# PSU5V-400mA.net
KiCad netlist of a schematic drawn in Altium Designer
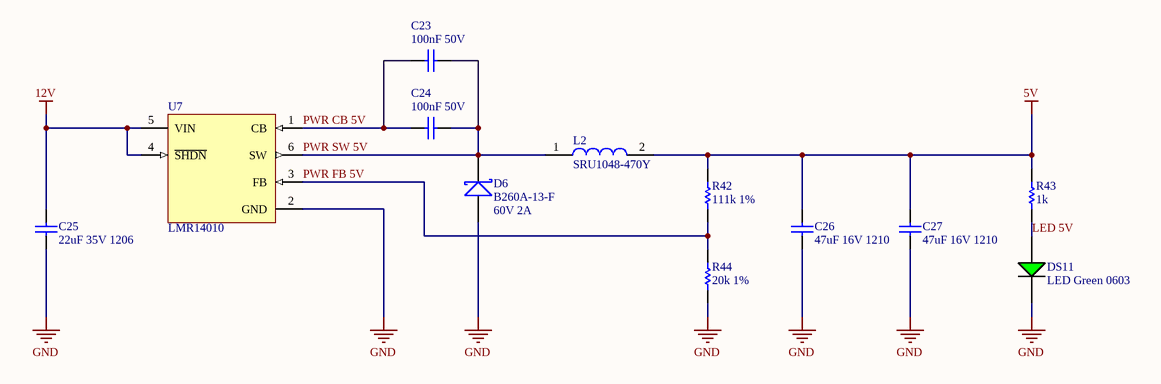
[diagram p0: PSU5V-400mA.SchDoc]

(export (version "E")
  (design (tool "Eeschema 10.0.6"))
  (components
    (comp (ref "C23")
      (value "100nF 50V")
      (footprint "Cap_Ceramic_0603")
      (description "Capacitor, Ceramic, SMD, 100nF, 50V, 5%, X7R, 0603")
      (libsource (lib "StandardCapacitors") (part "100nF 50V 5% X7R 0603"))
    )
    (comp (ref "C24")
      (value "100nF 50V")
      (footprint "Cap_Ceramic_0603")
      (description "Capacitor, Ceramic, SMD, 100nF, 50V, 5%, X7R, 0603")
      (libsource (lib "StandardCapacitors") (part "100nF 50V 5% X7R 0603"))
    )
    (comp (ref "C25")
      (value "22uF 35V 1206")
      (footprint "Cap_Ceramic_1206")
      (description "Capacitor, Ceramic, SMD, 22uF, 35V, 10%, X7R, 1206")
      (libsource (lib "StandardCapacitors") (part "22uF 35V 10% X7R 1206"))
    )
    (comp (ref "C26")
      (value "47uF 16V 1210")
      (footprint "Cap_Ceramic_1210")
      (description "Capacitor, Ceramic, SMD, 47uF, 16V, 5%, X7R, 1210")
      (libsource (lib "StandardCapacitors") (part "47uF 16V 10% X7R 1210"))
    )
    (comp (ref "C27")
      (value "47uF 16V 1210")
      (footprint "Cap_Ceramic_1210")
      (description "Capacitor, Ceramic, SMD, 47uF, 16V, 5%, X7R, 1210")
      (libsource (lib "StandardCapacitors") (part "47uF 16V 10% X7R 1210"))
    )
    (comp (ref "D6")
      (value "B260A-13-F")
      (footprint "SMA")
      (description "Diode, Schottky Barrier Rectifier, 60 V, 2 A, B260A-13-F")
      (libsource (lib "QUTMS_DiodeLibrary") (part "B260A-13-F"))
    )
    (comp (ref "DS11")
      (value "LED Green 0603")
      (footprint "LED GREEN 0603")
      (libsource (lib "QUTMS_LEDLibrary") (part "LED Green 0603"))
    )
    (comp (ref "L2")
      (value "SRU1048-470Y")
      (footprint "SRU1048")
      (description "Fixed Inductors 47uH 30% SMD 1048")
      (libsource (lib "QUTMS_InductorLibrary") (part "SRU1048-470Y"))
    )
    (comp (ref "R42")
      (value "111k 1%")
      (footprint "Res_ThinFilm_0603")
      (description "Resistor, SMD, 111k, 0.1W, 5%, 0603")
      (libsource (lib "StandardResistors") (part "111k 1% 0603"))
    )
    (comp (ref "R43")
      (value "1k")
      (footprint "Res_ThinFilm_0603")
      (description "Resistor, SMD, 1k, 0.1W, 5%, 0603")
      (libsource (lib "StandardResistors") (part "1k 5% 0603"))
    )
    (comp (ref "R44")
      (value "20k 1%")
      (footprint "Res_ThinFilm_0603")
      (description "Resistor, SMD, 20k, 0.1W, 1%, 0603")
      (libsource (lib "StandardResistors") (part "20k 1% 0603"))
    )
    (comp (ref "U7")
      (value "LMR14010")
      (footprint "LMR14010")
      (libsource (lib "QUTMS_PowerSupplyLibrary") (part "LMR14010"))
    )
  )
  (nets
    (net (code "1") (name "/LED 5V") (class "Default")
      (node (ref "DS11") (pin "1") (pinfunction "A_1") (pintype "passive"))
      (node (ref "R43") (pin "1") (pinfunction "1_1") (pintype "passive"))
    )
    (net (code "2") (name "/PWR CB 5V") (class "Default")
      (node (ref "C23") (pin "1") (pinfunction "1_1") (pintype "passive"))
      (node (ref "C24") (pin "1") (pinfunction "1_1") (pintype "passive"))
      (node (ref "U7") (pin "1") (pinfunction "CB_1") (pintype "input"))
    )
    (net (code "3") (name "/PWR FB 5V") (class "Default")
      (node (ref "R42") (pin "1") (pinfunction "1_1") (pintype "passive"))
      (node (ref "R44") (pin "2") (pinfunction "2_2") (pintype "passive"))
      (node (ref "U7") (pin "3") (pinfunction "FB_3") (pintype "input"))
    )
    (net (code "4") (name "/PWR SW 5V") (class "Default")
      (node (ref "C23") (pin "2") (pinfunction "2_2") (pintype "passive"))
      (node (ref "C24") (pin "2") (pinfunction "2_2") (pintype "passive"))
      (node (ref "D6") (pin "K") (pinfunction "K_K") (pintype "passive"))
      (node (ref "L2") (pin "1") (pinfunction "1_1") (pintype "passive"))
      (node (ref "U7") (pin "6") (pinfunction "SW_6") (pintype "output"))
    )
    (net (code "5") (name "5V") (class "Default")
      (node (ref "C26") (pin "2") (pinfunction "2_2") (pintype "passive"))
      (node (ref "C27") (pin "2") (pinfunction "2_2") (pintype "passive"))
      (node (ref "L2") (pin "2") (pinfunction "2_2") (pintype "passive"))
      (node (ref "R42") (pin "2") (pinfunction "2_2") (pintype "passive"))
      (node (ref "R43") (pin "2") (pinfunction "2_2") (pintype "passive"))
    )
    (net (code "6") (name "12V") (class "Default")
      (node (ref "C25") (pin "2") (pinfunction "2_2") (pintype "passive"))
      (node (ref "U7") (pin "4") (pinfunction "~{SHDN}_4") (pintype "input"))
      (node (ref "U7") (pin "5") (pinfunction "VIN_5") (pintype "power_in"))
    )
    (net (code "7") (name "GND") (class "Default")
      (node (ref "C25") (pin "1") (pinfunction "1_1") (pintype "passive"))
      (node (ref "C26") (pin "1") (pinfunction "1_1") (pintype "passive"))
      (node (ref "C27") (pin "1") (pinfunction "1_1") (pintype "passive"))
      (node (ref "D6") (pin "A") (pinfunction "A_A") (pintype "passive"))
      (node (ref "DS11") (pin "2") (pinfunction "C_2") (pintype "passive"))
      (node (ref "R44") (pin "1") (pinfunction "1_1") (pintype "passive"))
      (node (ref "U7") (pin "2") (pinfunction "GND_2") (pintype "power_in"))
    )
  )
)
